# PG06_Nuerosky.net
KiCad netlist of a schematic drawn in Altium Designer
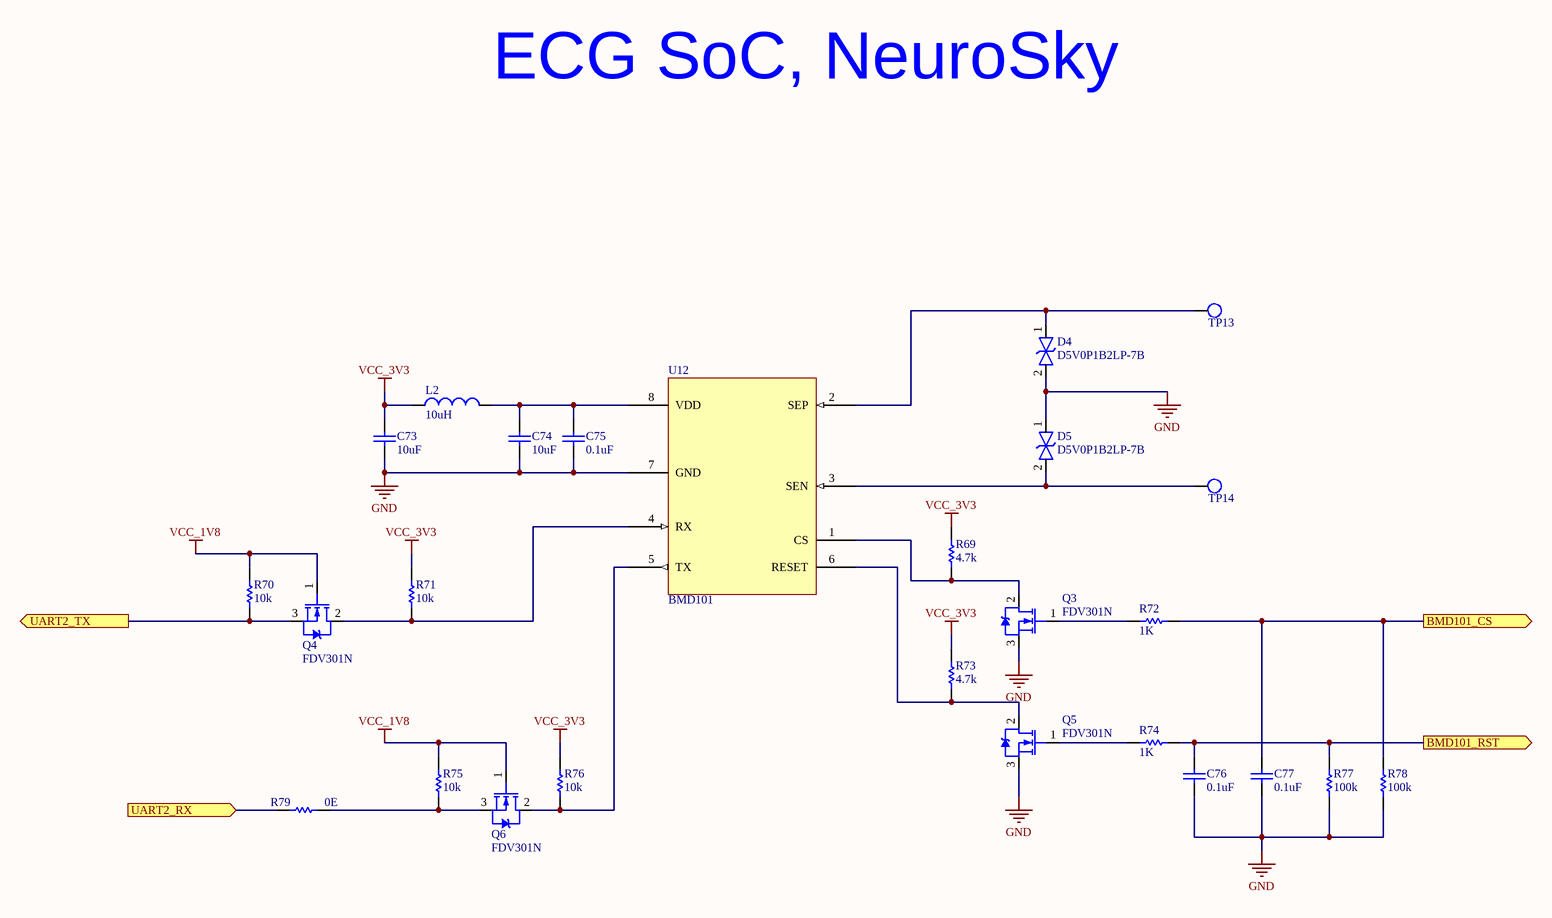
[diagram p0: PG06_Nuerosky.SchDoc]

(export (version "E")
  (design (tool "Eeschema 10.0.6"))
  (components
    (comp (ref "C73")
      (value "10uF")
      (footprint "0805C")
      (description "CAP CER 10UF 16V X7R 0805")
      (libsource (lib "Smart Ring Components") (part "CAP_0805_10uF_16V"))
    )
    (comp (ref "C74")
      (value "10uF")
      (footprint "0805C")
      (description "CAP CER 10UF 16V X7R 0805")
      (libsource (lib "Smart Ring Components") (part "CAP_0805_10uF_16V"))
    )
    (comp (ref "C75")
      (value "0.1uF")
      (footprint "0402C")
      (description "CAP CER 0.1UF 50V X7R 0402")
      (libsource (lib "Smart Ring Components") (part "CAP_0402_0.1uF_50V"))
    )
    (comp (ref "C76")
      (value "0.1uF")
      (footprint "0402C")
      (description "CAP CER 0.1UF 50V X7R 0402")
      (libsource (lib "Smart Ring Components") (part "CAP_0402_0.1uF_50V"))
    )
    (comp (ref "C77")
      (value "0.1uF")
      (footprint "0402C")
      (description "CAP CER 0.1UF 50V X7R 0402")
      (libsource (lib "Smart Ring Components") (part "CAP_0402_0.1uF_50V"))
    )
    (comp (ref "D4")
      (value "D5V0P1B2LP-7B")
      (footprint "D5V0P1B2LP-7B")
      (description "TVS DIODE 5.5VWM 13VC DFN1006-2")
      (fields (field (name "MFR") "Diodes Incorporated"))
      (libsource (lib "Smart Ring Components") (part "TVS_D5V0P1B2LP-7B"))
    )
    (comp (ref "D5")
      (value "D5V0P1B2LP-7B")
      (footprint "D5V0P1B2LP-7B")
      (description "TVS DIODE 5.5VWM 13VC DFN1006-2")
      (fields (field (name "MFR") "Diodes Incorporated"))
      (libsource (lib "Smart Ring Components") (part "TVS_D5V0P1B2LP-7B"))
    )
    (comp (ref "L2")
      (value "10uH")
      (footprint "NR6028T3R0N")
      (description "WE-PMI POWER MULTILAYER INDUCTOR")
      (fields (field (name "MFR") "Würth Elektronik") (field (name "MPN") "74479777310A"))
      (libsource (lib "Smart Ring Components") (part "IND_10uH"))
    )
    (comp (ref "Q3")
      (value "FDV301N")
      (footprint "SOT_23")
      (description "MOSFET N-CH 25V 220MA SOT23")
      (fields (field (name "MFR") "onsemi"))
      (libsource (lib "Smart Ring Components") (part "NMOS_FDV301N"))
    )
    (comp (ref "Q4")
      (value "FDV301N")
      (footprint "SOT_23")
      (description "MOSFET N-CH 25V 220MA SOT23")
      (fields (field (name "MFR") "onsemi"))
      (libsource (lib "Smart Ring Components") (part "NMOS_FDV301N"))
    )
    (comp (ref "Q5")
      (value "FDV301N")
      (footprint "SOT_23")
      (description "MOSFET N-CH 25V 220MA SOT23")
      (fields (field (name "MFR") "onsemi"))
      (libsource (lib "Smart Ring Components") (part "NMOS_FDV301N"))
    )
    (comp (ref "Q6")
      (value "FDV301N")
      (footprint "SOT_23")
      (description "MOSFET N-CH 25V 220MA SOT23")
      (fields (field (name "MFR") "onsemi"))
      (libsource (lib "Smart Ring Components") (part "NMOS_FDV301N"))
    )
    (comp (ref "R69")
      (value "4.7k")
      (footprint "0402R")
      (description "RES 4.7K OHM 1% 1/16W 0402")
      (fields (field (name "MFR") "Generic"))
      (libsource (lib "Smart Ring Components") (part "RES_0402_4.7k"))
    )
    (comp (ref "R70")
      (value "10k")
      (footprint "0402R")
      (description "RES SMD 10K OHM 1% 1/16W 0402")
      (fields (field (name "MFR") "Generic"))
      (libsource (lib "Smart Ring Components") (part "RES_0402_10k"))
    )
    (comp (ref "R71")
      (value "10k")
      (footprint "0402R")
      (description "RES SMD 10K OHM 1% 1/16W 0402")
      (fields (field (name "MFR") "Generic"))
      (libsource (lib "Smart Ring Components") (part "RES_0402_10k"))
    )
    (comp (ref "R72")
      (value "1K")
      (footprint "0402R")
      (description "RES SMD 1K OHM 1% 1/16W 0402")
      (fields (field (name "MFR") "Generic"))
      (libsource (lib "Smart Ring Components") (part "RES_0402_1k"))
    )
    (comp (ref "R73")
      (value "4.7k")
      (footprint "0402R")
      (description "RES 4.7K OHM 1% 1/16W 0402")
      (fields (field (name "MFR") "Generic"))
      (libsource (lib "Smart Ring Components") (part "RES_0402_4.7k"))
    )
    (comp (ref "R74")
      (value "1K")
      (footprint "0402R")
      (description "RES SMD 1K OHM 1% 1/16W 0402")
      (fields (field (name "MFR") "Generic"))
      (libsource (lib "Smart Ring Components") (part "RES_0402_1k"))
    )
    (comp (ref "R75")
      (value "10k")
      (footprint "0402R")
      (description "RES SMD 10K OHM 1% 1/16W 0402")
      (fields (field (name "MFR") "Generic"))
      (libsource (lib "Smart Ring Components") (part "RES_0402_10k"))
    )
    (comp (ref "R76")
      (value "10k")
      (footprint "0402R")
      (description "RES SMD 10K OHM 1% 1/16W 0402")
      (fields (field (name "MFR") "Generic"))
      (libsource (lib "Smart Ring Components") (part "RES_0402_10k"))
    )
    (comp (ref "R77")
      (value "100k")
      (footprint "0402R")
      (description "RES 100K OHM 1% 1/16W 0402")
      (fields (field (name "MFR") "Generic"))
      (libsource (lib "Smart Ring Components") (part "RES_0402_100k"))
    )
    (comp (ref "R78")
      (value "100k")
      (footprint "0402R")
      (description "RES 100K OHM 1% 1/16W 0402")
      (fields (field (name "MFR") "Generic"))
      (libsource (lib "Smart Ring Components") (part "RES_0402_100k"))
    )
    (comp (ref "R79")
      (value "0E")
      (footprint "0402R")
      (description "RES 0 OHM JUMPER 1/16W 0402")
      (fields (field (name "MFR") "Generic"))
      (libsource (lib "Smart Ring Components") (part "RES_0402_0E"))
    )
    (comp (ref "TP13")
      (value "Test_Point")
      (footprint "TP_SMD")
      (libsource (lib "Smart Ring Components") (part "Test_Point_1"))
    )
    (comp (ref "TP14")
      (value "Test_Point")
      (footprint "TP_SMD")
      (libsource (lib "Smart Ring Components") (part "Test_Point_1"))
    )
    (comp (ref "U12")
      (value "BMD101")
      (footprint "BMD101")
      (description "Mixed Signal SoC with Integrated AFE, DSP functions and UART")
      (fields (field (name "MFR") "NeuroSky"))
      (libsource (lib "Smart Ring Components") (part "Bio-Signal_SoC_BMD101"))
    )
  )
  (nets
    (net (code "1") (name "/BMD101_CS") (class "Default")
      (node (ref "C77") (pin "2") (pinfunction "2_2") (pintype "passive"))
      (node (ref "R72") (pin "2") (pinfunction "2_2") (pintype "passive"))
      (node (ref "R78") (pin "2") (pinfunction "2_2") (pintype "passive"))
    )
    (net (code "2") (name "/BMD101_RST") (class "Default")
      (node (ref "C76") (pin "2") (pinfunction "2_2") (pintype "passive"))
      (node (ref "R74") (pin "2") (pinfunction "2_2") (pintype "passive"))
      (node (ref "R77") (pin "2") (pinfunction "2_2") (pintype "passive"))
    )
    (net (code "3") (name "/UART2_RX") (class "Default")
      (node (ref "R79") (pin "1") (pinfunction "1_1") (pintype "passive"))
    )
    (net (code "4") (name "/UART2_TX") (class "Default")
      (node (ref "Q4") (pin "3") (pinfunction "S_3") (pintype "passive"))
      (node (ref "R70") (pin "1") (pinfunction "1_1") (pintype "passive"))
    )
    (net (code "5") (name "GND") (class "Default")
      (node (ref "C73") (pin "1") (pinfunction "1_1") (pintype "passive"))
      (node (ref "C74") (pin "1") (pinfunction "1_1") (pintype "passive"))
      (node (ref "C75") (pin "1") (pinfunction "1_1") (pintype "passive"))
      (node (ref "C76") (pin "1") (pinfunction "1_1") (pintype "passive"))
      (node (ref "C77") (pin "1") (pinfunction "1_1") (pintype "passive"))
      (node (ref "D4") (pin "2") (pinfunction "2_2") (pintype "passive"))
      (node (ref "D5") (pin "1") (pinfunction "1_1") (pintype "passive"))
      (node (ref "Q3") (pin "3") (pinfunction "S_3") (pintype "passive"))
      (node (ref "Q5") (pin "3") (pinfunction "S_3") (pintype "passive"))
      (node (ref "R77") (pin "1") (pinfunction "1_1") (pintype "passive"))
      (node (ref "R78") (pin "1") (pinfunction "1_1") (pintype "passive"))
      (node (ref "U12") (pin "7") (pinfunction "GND_7") (pintype "power_in"))
    )
    (net (code "6") (name "Net-(Q3-D)") (class "Default")
      (node (ref "Q3") (pin "2") (pinfunction "D_2") (pintype "passive"))
      (node (ref "R69") (pin "1") (pinfunction "1_1") (pintype "passive"))
      (node (ref "U12") (pin "1") (pinfunction "CS_1") (pintype "passive"))
    )
    (net (code "7") (name "Net-(Q3-G)") (class "Default")
      (node (ref "Q3") (pin "1") (pinfunction "G_1") (pintype "passive"))
      (node (ref "R72") (pin "1") (pinfunction "1_1") (pintype "passive"))
    )
    (net (code "8") (name "Net-(Q4-D)") (class "Default")
      (node (ref "Q4") (pin "2") (pinfunction "D_2") (pintype "passive"))
      (node (ref "R71") (pin "1") (pinfunction "1_1") (pintype "passive"))
      (node (ref "U12") (pin "4") (pinfunction "RX_4") (pintype "input"))
    )
    (net (code "9") (name "Net-(Q5-D)") (class "Default")
      (node (ref "Q5") (pin "2") (pinfunction "D_2") (pintype "passive"))
      (node (ref "R73") (pin "1") (pinfunction "1_1") (pintype "passive"))
      (node (ref "U12") (pin "6") (pinfunction "RESET_6") (pintype "passive"))
    )
    (net (code "10") (name "Net-(Q5-G)") (class "Default")
      (node (ref "Q5") (pin "1") (pinfunction "G_1") (pintype "passive"))
      (node (ref "R74") (pin "1") (pinfunction "1_1") (pintype "passive"))
    )
    (net (code "11") (name "Net-(Q6-D)") (class "Default")
      (node (ref "Q6") (pin "2") (pinfunction "D_2") (pintype "passive"))
      (node (ref "R76") (pin "1") (pinfunction "1_1") (pintype "passive"))
      (node (ref "U12") (pin "5") (pinfunction "TX_5") (pintype "output"))
    )
    (net (code "12") (name "Net-(Q6-S)") (class "Default")
      (node (ref "Q6") (pin "3") (pinfunction "S_3") (pintype "passive"))
      (node (ref "R75") (pin "1") (pinfunction "1_1") (pintype "passive"))
      (node (ref "R79") (pin "2") (pinfunction "2_2") (pintype "passive"))
    )
    (net (code "13") (name "Net-(U12-SEN)") (class "Default")
      (node (ref "D5") (pin "2") (pinfunction "2_2") (pintype "passive"))
      (node (ref "TP14") (pin "1") (pintype "passive"))
      (node (ref "U12") (pin "3") (pinfunction "SEN_3") (pintype "input"))
    )
    (net (code "14") (name "Net-(U12-SEP)") (class "Default")
      (node (ref "D4") (pin "1") (pinfunction "1_1") (pintype "passive"))
      (node (ref "TP13") (pin "1") (pintype "passive"))
      (node (ref "U12") (pin "2") (pinfunction "SEP_2") (pintype "input"))
    )
    (net (code "15") (name "Net-(U12-VDD)") (class "Default")
      (node (ref "C74") (pin "2") (pinfunction "2_2") (pintype "passive"))
      (node (ref "C75") (pin "2") (pinfunction "2_2") (pintype "passive"))
      (node (ref "L2") (pin "2") (pinfunction "2_2") (pintype "passive"))
      (node (ref "U12") (pin "8") (pinfunction "VDD_8") (pintype "power_in"))
    )
    (net (code "16") (name "VCC_1V8") (class "Default")
      (node (ref "Q4") (pin "1") (pinfunction "G_1") (pintype "passive"))
      (node (ref "Q6") (pin "1") (pinfunction "G_1") (pintype "passive"))
      (node (ref "R70") (pin "2") (pinfunction "2_2") (pintype "passive"))
      (node (ref "R75") (pin "2") (pinfunction "2_2") (pintype "passive"))
    )
    (net (code "17") (name "VCC_3V3") (class "Default")
      (node (ref "C73") (pin "2") (pinfunction "2_2") (pintype "passive"))
      (node (ref "L2") (pin "1") (pinfunction "1_1") (pintype "passive"))
      (node (ref "R69") (pin "2") (pinfunction "2_2") (pintype "passive"))
      (node (ref "R71") (pin "2") (pinfunction "2_2") (pintype "passive"))
      (node (ref "R73") (pin "2") (pinfunction "2_2") (pintype "passive"))
      (node (ref "R76") (pin "2") (pinfunction "2_2") (pintype "passive"))
    )
  )
)
